# CMoy-Pro-V_0_0_1A.net
KiCad netlist of a schematic drawn in EAGLE
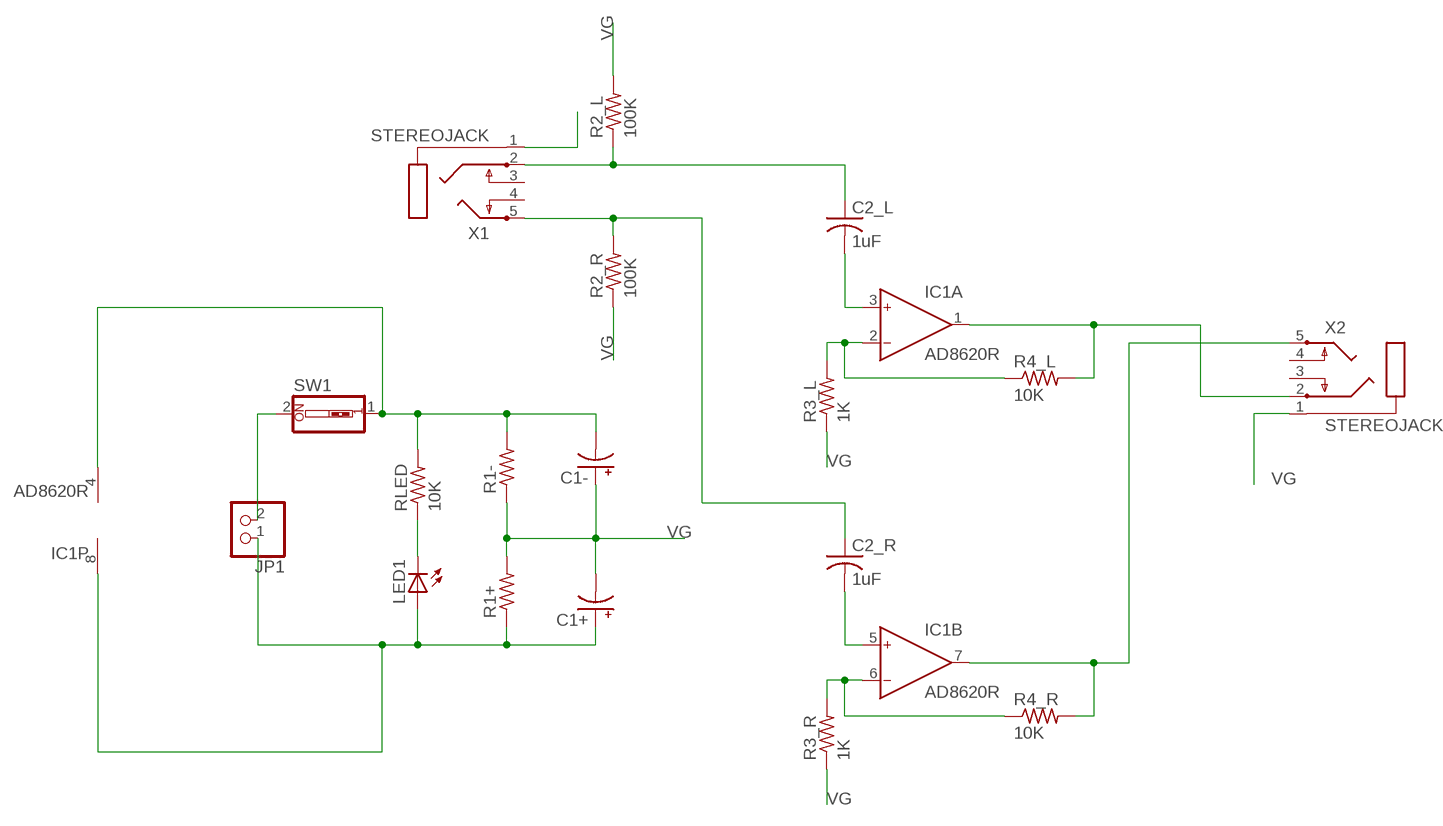
[diagram p0: schematic, sheet 1]

(export (version "E")
  (design (tool "Eeschema 10.0.6"))
  (components
    (comp (ref "C1+")
      (value "CPOL-USE2.5-6")
      (footprint "eagle-import:E2,5-6")
      (libsource (lib "eagle-import") (part "CPOL-USE2.5-6"))
    )
    (comp (ref "C1-")
      (value "CPOL-USE2.5-6")
      (footprint "eagle-import:E2,5-6")
      (libsource (lib "eagle-import") (part "CPOL-USE2.5-6"))
    )
    (comp (ref "C2_L")
      (value "1uF")
      (footprint "eagle-import:C102-043X133")
      (libsource (lib "eagle-import") (part "C-US102-043X133"))
    )
    (comp (ref "C2_R")
      (value "1uF")
      (footprint "eagle-import:C102-043X133")
      (libsource (lib "eagle-import") (part "C-US102-043X133"))
    )
    (comp (ref "IC1")
      (value "AD8620R")
      (footprint "eagle-import:SO8")
      (fields (field (name "MF") "ALTERA CORPORATION") (field (name "MPN") "AD8620ARZ"))
      (libsource (lib "eagle-import") (part "AD8620R"))
    )
    (comp (ref "JP1")
      (value "PINHD-1X2")
      (footprint "eagle-import:1X02")
      (libsource (lib "eagle-import") (part "PINHD-1X2"))
    )
    (comp (ref "LED1")
      (value "LED3MM")
      (footprint "eagle-import:LED3MM")
      (libsource (lib "eagle-import") (part "LED3MM"))
    )
    (comp (ref "R1+")
      (value "R-US_0207/7")
      (footprint "eagle-import:0207_7")
      (libsource (lib "eagle-import") (part "R-US_0207/7"))
    )
    (comp (ref "R1-")
      (value "R-US_0207/7")
      (footprint "eagle-import:0207_7")
      (libsource (lib "eagle-import") (part "R-US_0207/7"))
    )
    (comp (ref "R2_L")
      (value "100K")
      (footprint "eagle-import:0207_7")
      (libsource (lib "eagle-import") (part "R-US_0207/7"))
    )
    (comp (ref "R2_R")
      (value "100K")
      (footprint "eagle-import:0207_7")
      (libsource (lib "eagle-import") (part "R-US_0207/7"))
    )
    (comp (ref "R3_L")
      (value "1K")
      (footprint "eagle-import:0207_7")
      (libsource (lib "eagle-import") (part "R-US_0207/7"))
    )
    (comp (ref "R3_R")
      (value "1K")
      (footprint "eagle-import:0207_7")
      (libsource (lib "eagle-import") (part "R-US_0207/7"))
    )
    (comp (ref "R4_L")
      (value "10K")
      (footprint "eagle-import:0207_7")
      (libsource (lib "eagle-import") (part "R-US_0207/7"))
    )
    (comp (ref "R4_R")
      (value "10K")
      (footprint "eagle-import:0207_7")
      (libsource (lib "eagle-import") (part "R-US_0207/7"))
    )
    (comp (ref "RLED")
      (value "10K")
      (footprint "eagle-import:0207_7")
      (libsource (lib "eagle-import") (part "R-US_0207/7"))
    )
    (comp (ref "SW1")
      (value "SW_DIP-1")
      (footprint "eagle-import:EDG-01")
      (libsource (lib "eagle-import") (part "SW_DIP-1"))
    )
    (comp (ref "X1")
      (value "STEREOJACK")
      (footprint "eagle-import:STX3100")
      (libsource (lib "eagle-import") (part "STEREOJACK"))
    )
    (comp (ref "X2")
      (value "STEREOJACK")
      (footprint "eagle-import:STX3100")
      (libsource (lib "eagle-import") (part "STEREOJACK"))
    )
  )
  (nets
    (net (code "1") (name "/VG") (class "Default")
      (node (ref "C1+") (pin "-") (pinfunction "-_-") (pintype "passive"))
      (node (ref "C1-") (pin "+") (pinfunction "+_+") (pintype "passive"))
      (node (ref "R1+") (pin "2") (pinfunction "2_2") (pintype "passive"))
      (node (ref "R1-") (pin "1") (pinfunction "1_1") (pintype "passive"))
      (node (ref "R2_L") (pin "2") (pinfunction "2_2") (pintype "passive"))
      (node (ref "R2_R") (pin "1") (pinfunction "1_1") (pintype "passive"))
      (node (ref "R3_L") (pin "1") (pinfunction "1_1") (pintype "passive"))
      (node (ref "R3_R") (pin "1") (pinfunction "1_1") (pintype "passive"))
      (node (ref "X1") (pin "1") (pinfunction "1_1") (pintype "passive"))
      (node (ref "X2") (pin "1") (pinfunction "1_1") (pintype "passive"))
    )
    (net (code "2") (name "Net-(C2_L-Pad1)") (class "Default")
      (node (ref "C2_L") (pin "1") (pinfunction "1_1") (pintype "passive"))
      (node (ref "R2_L") (pin "1") (pinfunction "1_1") (pintype "passive"))
      (node (ref "X1") (pin "2") (pinfunction "2_2") (pintype "passive"))
    )
    (net (code "3") (name "Net-(C2_R-Pad1)") (class "Default")
      (node (ref "C2_R") (pin "1") (pinfunction "1_1") (pintype "passive"))
      (node (ref "R2_R") (pin "2") (pinfunction "2_2") (pintype "passive"))
      (node (ref "X1") (pin "5") (pinfunction "5_5") (pintype "passive"))
    )
    (net (code "4") (name "Net-(IC1A-IN+)") (class "Default")
      (node (ref "C2_L") (pin "2") (pinfunction "2_2") (pintype "passive"))
      (node (ref "IC1") (pin "3") (pinfunction "IN+_3") (pintype "input"))
    )
    (net (code "5") (name "Net-(IC1A-IN-)") (class "Default")
      (node (ref "IC1") (pin "2") (pinfunction "IN-_2") (pintype "input"))
      (node (ref "R3_L") (pin "2") (pinfunction "2_2") (pintype "passive"))
      (node (ref "R4_L") (pin "1") (pinfunction "1_1") (pintype "passive"))
    )
    (net (code "6") (name "Net-(IC1A-OUT)") (class "Default")
      (node (ref "IC1") (pin "1") (pinfunction "OUT_1") (pintype "output"))
      (node (ref "R4_L") (pin "2") (pinfunction "2_2") (pintype "passive"))
      (node (ref "X2") (pin "2") (pinfunction "2_2") (pintype "passive"))
    )
    (net (code "7") (name "Net-(IC1B-IN+)") (class "Default")
      (node (ref "C2_R") (pin "2") (pinfunction "2_2") (pintype "passive"))
      (node (ref "IC1") (pin "5") (pinfunction "IN+_5") (pintype "input"))
    )
    (net (code "8") (name "Net-(IC1B-IN-)") (class "Default")
      (node (ref "IC1") (pin "6") (pinfunction "IN-_6") (pintype "input"))
      (node (ref "R3_R") (pin "2") (pinfunction "2_2") (pintype "passive"))
      (node (ref "R4_R") (pin "1") (pinfunction "1_1") (pintype "passive"))
    )
    (net (code "9") (name "Net-(IC1B-OUT)") (class "Default")
      (node (ref "IC1") (pin "7") (pinfunction "OUT_7") (pintype "output"))
      (node (ref "R4_R") (pin "2") (pinfunction "2_2") (pintype "passive"))
      (node (ref "X2") (pin "5") (pinfunction "5_5") (pintype "passive"))
    )
    (net (code "10") (name "Net-(IC1C-V+)") (class "Default")
      (node (ref "C1+") (pin "+") (pinfunction "+_+") (pintype "passive"))
      (node (ref "IC1") (pin "8") (pinfunction "V+_8") (pintype "power_in"))
      (node (ref "JP1") (pin "1") (pinfunction "1_1") (pintype "passive"))
      (node (ref "LED1") (pin "A") (pinfunction "A_A") (pintype "passive"))
      (node (ref "R1+") (pin "1") (pinfunction "1_1") (pintype "passive"))
    )
    (net (code "11") (name "Net-(IC1C-V-)") (class "Default")
      (node (ref "C1-") (pin "-") (pinfunction "-_-") (pintype "passive"))
      (node (ref "IC1") (pin "4") (pinfunction "V-_4") (pintype "power_in"))
      (node (ref "R1-") (pin "2") (pinfunction "2_2") (pintype "passive"))
      (node (ref "RLED") (pin "2") (pinfunction "2_2") (pintype "passive"))
      (node (ref "SW1") (pin "1") (pinfunction "1_1") (pintype "passive"))
    )
    (net (code "12") (name "Net-(JP1-Pad2)") (class "Default")
      (node (ref "JP1") (pin "2") (pinfunction "2_2") (pintype "passive"))
      (node (ref "SW1") (pin "2") (pinfunction "2_2") (pintype "passive"))
    )
    (net (code "13") (name "Net-(LED1-C)") (class "Default")
      (node (ref "LED1") (pin "K") (pinfunction "C_K") (pintype "passive"))
      (node (ref "RLED") (pin "1") (pinfunction "1_1") (pintype "passive"))
    )
    (net (code "14") (name "unconnected-(X1-Pad3)") (class "Default")
      (node (ref "X1") (pin "3") (pinfunction "3_3") (pintype "passive"))
    )
    (net (code "15") (name "unconnected-(X1-Pad4)") (class "Default")
      (node (ref "X1") (pin "4") (pinfunction "4_4") (pintype "passive"))
    )
    (net (code "16") (name "unconnected-(X2-Pad3)") (class "Default")
      (node (ref "X2") (pin "3") (pinfunction "3_3") (pintype "passive"))
    )
    (net (code "17") (name "unconnected-(X2-Pad4)") (class "Default")
      (node (ref "X2") (pin "4") (pinfunction "4_4") (pintype "passive"))
    )
  )
)
